# W682A.net
KiCad netlist of a schematic drawn in EAGLE
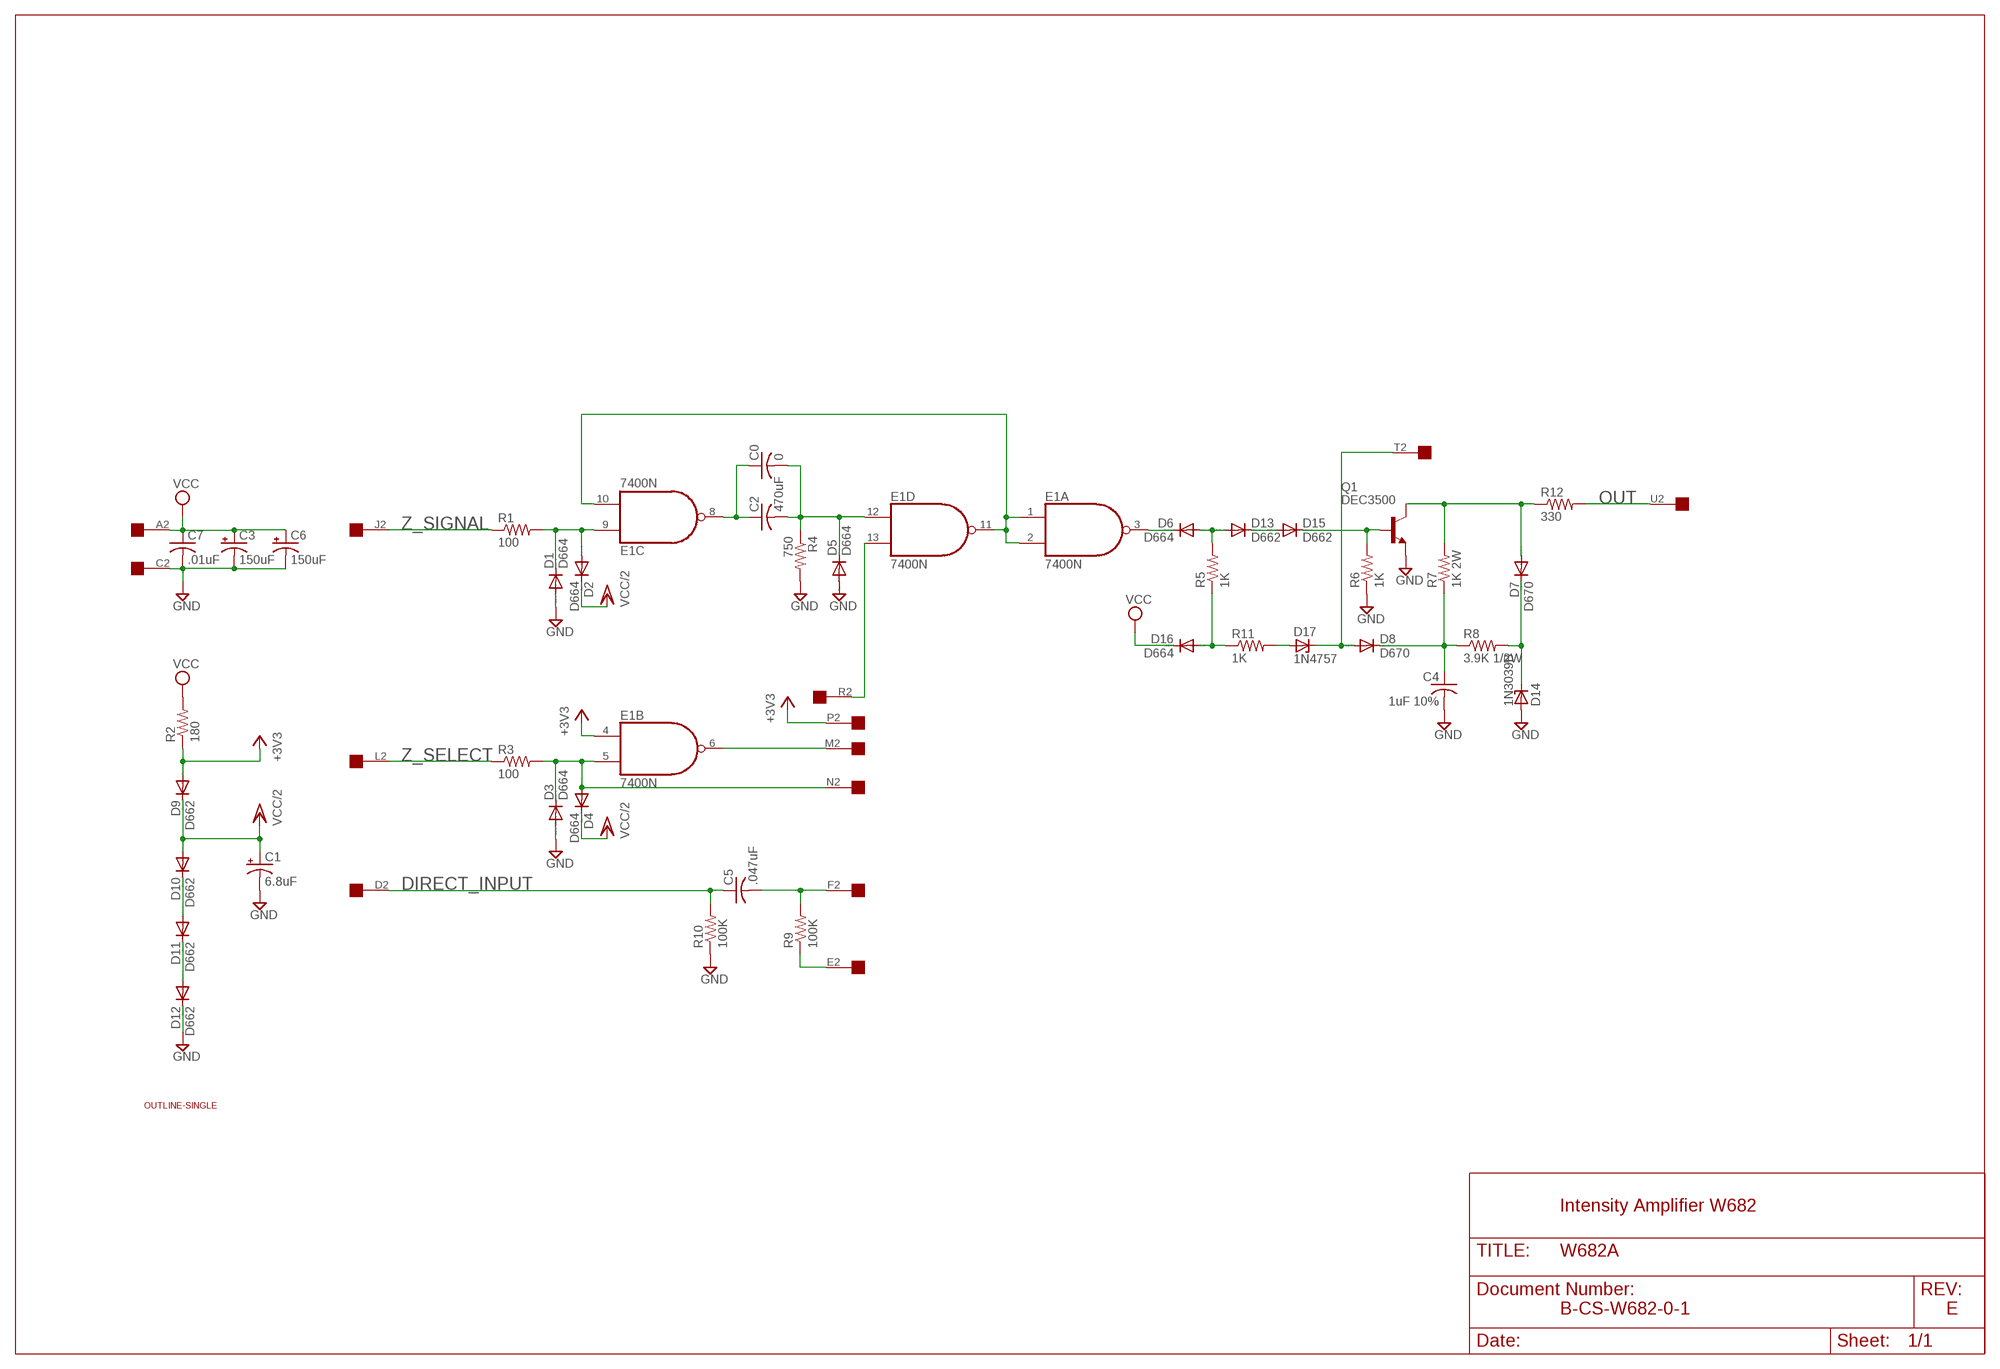
[diagram p0: schematic, sheet 1]

(export (version "E")
  (design (tool "Eeschema 10.0.6"))
  (components
    (comp (ref "C0")
      (value "0")
      (footprint "eagle-import:C050-025X075")
      (libsource (lib "eagle-import") (part "C-US050-025X075"))
    )
    (comp (ref "C1")
      (value "6.8uF")
      (footprint "eagle-import:E12-8")
      (libsource (lib "eagle-import") (part "CPOL-USE20-8AXIAL"))
    )
    (comp (ref "C2")
      (value "470uF")
      (footprint "eagle-import:C050-025X075")
      (libsource (lib "eagle-import") (part "C-US050-025X075"))
    )
    (comp (ref "C3")
      (value "150uF")
      (footprint "eagle-import:E22-9")
      (libsource (lib "eagle-import") (part "CPOL-USE22-9AXIAL"))
    )
    (comp (ref "C4")
      (value "1uF 10%")
      (footprint "eagle-import:C325-137X374")
      (libsource (lib "eagle-import") (part "C-US325-137X374"))
    )
    (comp (ref "C5")
      (value ".047uF")
      (footprint "eagle-import:C275-093X316")
      (libsource (lib "eagle-import") (part "C-US275-093X316"))
    )
    (comp (ref "C6")
      (value "150uF")
      (footprint "eagle-import:E22-9")
      (libsource (lib "eagle-import") (part "CPOL-USE22-9AXIAL"))
    )
    (comp (ref "C7")
      (value ".01uF")
      (footprint "eagle-import:C050-025X075")
      (libsource (lib "eagle-import") (part "C-US050-025X075"))
    )
    (comp (ref "D1")
      (value "D664")
      (footprint "eagle-import:DO35-10")
      (libsource (lib "eagle-import") (part "DIODE-DO35-10"))
    )
    (comp (ref "D2")
      (value "D664")
      (footprint "eagle-import:DO35-10")
      (libsource (lib "eagle-import") (part "DIODE-DO35-10"))
    )
    (comp (ref "D3")
      (value "D664")
      (footprint "eagle-import:DO35-10")
      (libsource (lib "eagle-import") (part "DIODE-DO35-10"))
    )
    (comp (ref "D4")
      (value "D664")
      (footprint "eagle-import:DO35-10")
      (libsource (lib "eagle-import") (part "DIODE-DO35-10"))
    )
    (comp (ref "D5")
      (value "D664")
      (footprint "eagle-import:DO35-10")
      (libsource (lib "eagle-import") (part "DIODE-DO35-10"))
    )
    (comp (ref "D6")
      (value "D664")
      (footprint "eagle-import:DO35-10")
      (libsource (lib "eagle-import") (part "DIODE-DO35-10"))
    )
    (comp (ref "D7")
      (value "D670")
      (footprint "eagle-import:DO41-10")
      (libsource (lib "eagle-import") (part "DIODE-DO41-10"))
    )
    (comp (ref "D8")
      (value "D670")
      (footprint "eagle-import:DO41-10")
      (libsource (lib "eagle-import") (part "DIODE-DO41-10"))
    )
    (comp (ref "D9")
      (value "D662")
      (footprint "eagle-import:DO35-10")
      (libsource (lib "eagle-import") (part "DIODE-DO35-10"))
    )
    (comp (ref "D10")
      (value "D662")
      (footprint "eagle-import:DO35-10")
      (libsource (lib "eagle-import") (part "DIODE-DO35-10"))
    )
    (comp (ref "D11")
      (value "D662")
      (footprint "eagle-import:DO35-10")
      (libsource (lib "eagle-import") (part "DIODE-DO35-10"))
    )
    (comp (ref "D12")
      (value "D662")
      (footprint "eagle-import:DO35-10")
      (libsource (lib "eagle-import") (part "DIODE-DO35-10"))
    )
    (comp (ref "D13")
      (value "D662")
      (footprint "eagle-import:DO35-10")
      (libsource (lib "eagle-import") (part "DIODE-DO35-10"))
    )
    (comp (ref "D14")
      (value "1N3039B")
      (footprint "eagle-import:ZDIO12.5")
      (libsource (lib "eagle-import") (part "ZENER-DIODEZD-12.5"))
    )
    (comp (ref "D15")
      (value "D662")
      (footprint "eagle-import:DO35-10")
      (libsource (lib "eagle-import") (part "DIODE-DO35-10"))
    )
    (comp (ref "D16")
      (value "D664")
      (footprint "eagle-import:DO35-10")
      (libsource (lib "eagle-import") (part "DIODE-DO35-10"))
    )
    (comp (ref "D17")
      (value "1N4757")
      (footprint "eagle-import:ZDIO12.5")
      (libsource (lib "eagle-import") (part "ZENER-DIODEZD-12.5"))
    )
    (comp (ref "E1")
      (value "7400N")
      (footprint "eagle-import:DIL14")
      (libsource (lib "eagle-import") (part "7400N"))
    )
    (comp (ref "Q1")
      (value "DEC3500")
      (footprint "eagle-import:TO39")
      (libsource (lib "eagle-import") (part "-NPN-TO39-EBC2N2102"))
    )
    (comp (ref "R1")
      (value "100")
      (footprint "eagle-import:0207_10")
      (libsource (lib "eagle-import") (part "R-US_0207/10"))
    )
    (comp (ref "R2")
      (value "180")
      (footprint "eagle-import:0207_10")
      (libsource (lib "eagle-import") (part "R-US_0207/10"))
    )
    (comp (ref "R3")
      (value "100")
      (footprint "eagle-import:0207_10")
      (libsource (lib "eagle-import") (part "R-US_0207/10"))
    )
    (comp (ref "R4")
      (value "750")
      (footprint "eagle-import:0207_10")
      (libsource (lib "eagle-import") (part "R-US_0207/10"))
    )
    (comp (ref "R5")
      (value "1K")
      (footprint "eagle-import:0207_10")
      (libsource (lib "eagle-import") (part "R-US_0207/10"))
    )
    (comp (ref "R6")
      (value "1K")
      (footprint "eagle-import:0207_10")
      (libsource (lib "eagle-import") (part "R-US_0207/10"))
    )
    (comp (ref "R7")
      (value "1K 2W")
      (footprint "eagle-import:0818_25")
      (libsource (lib "eagle-import") (part "R-US_0818/25"))
    )
    (comp (ref "R8")
      (value "3.9K 1/2W")
      (footprint "eagle-import:0411_15")
      (libsource (lib "eagle-import") (part "R-US_0411/15"))
    )
    (comp (ref "R9")
      (value "100K")
      (footprint "eagle-import:0207_10")
      (libsource (lib "eagle-import") (part "R-US_0207/10"))
    )
    (comp (ref "R10")
      (value "100K")
      (footprint "eagle-import:0207_10")
      (libsource (lib "eagle-import") (part "R-US_0207/10"))
    )
    (comp (ref "R11")
      (value "1K")
      (footprint "eagle-import:0207_10")
      (libsource (lib "eagle-import") (part "R-US_0207/10"))
    )
    (comp (ref "R12")
      (value "330")
      (footprint "eagle-import:0207_10")
      (libsource (lib "eagle-import") (part "R-US_0207/10"))
    )
    (comp (ref "U$1")
      (value "OUTLINE-SINGLE")
      (footprint "eagle-import:SINGLE")
      (libsource (lib "eagle-import") (part "OUTLINE-SINGLE"))
    )
    (comp (ref "U$2")
      (value "EDGE-1")
      (footprint "eagle-import:EDGE-CON1")
      (libsource (lib "eagle-import") (part "EDGE-1"))
    )
  )
  (nets
    (net (code "1") (name "+3V3") (class "Default")
      (node (ref "D9") (pin "A") (pinfunction "A_A") (pintype "passive"))
      (node (ref "E1") (pin "4") (pinfunction "I0_4") (pintype "input"))
      (node (ref "R2") (pin "1") (pinfunction "1_1") (pintype "passive"))
      (node (ref "U$2") (pin "P2") (pinfunction "1_P2") (pintype "bidirectional"))
    )
    (net (code "2") (name "/DIRECT_INPUT") (class "Default")
      (node (ref "C5") (pin "1") (pinfunction "1_1") (pintype "passive"))
      (node (ref "R10") (pin "2") (pinfunction "2_2") (pintype "passive"))
      (node (ref "U$2") (pin "D2") (pinfunction "1_D2") (pintype "bidirectional"))
    )
    (net (code "3") (name "/OUT") (class "Default")
      (node (ref "R12") (pin "2") (pinfunction "2_2") (pintype "passive"))
      (node (ref "U$2") (pin "U2") (pinfunction "1_U2") (pintype "bidirectional"))
    )
    (net (code "4") (name "/Z_SELECT") (class "Default")
      (node (ref "R3") (pin "1") (pinfunction "1_1") (pintype "passive"))
      (node (ref "U$2") (pin "L2") (pinfunction "1_L2") (pintype "bidirectional"))
    )
    (net (code "5") (name "/Z_SIGNAL") (class "Default")
      (node (ref "R1") (pin "1") (pinfunction "1_1") (pintype "passive"))
      (node (ref "U$2") (pin "J2") (pinfunction "1_J2") (pintype "bidirectional"))
    )
    (net (code "6") (name "GND") (class "Default")
      (node (ref "C1") (pin "-") (pinfunction "-_-") (pintype "passive"))
      (node (ref "C3") (pin "-") (pinfunction "-_-") (pintype "passive"))
      (node (ref "C4") (pin "2") (pinfunction "2_2") (pintype "passive"))
      (node (ref "C6") (pin "-") (pinfunction "-_-") (pintype "passive"))
      (node (ref "C7") (pin "2") (pinfunction "2_2") (pintype "passive"))
      (node (ref "D1") (pin "A") (pinfunction "A_A") (pintype "passive"))
      (node (ref "D12") (pin "C") (pinfunction "C_C") (pintype "passive"))
      (node (ref "D14") (pin "A") (pinfunction "A_A") (pintype "passive"))
      (node (ref "D3") (pin "A") (pinfunction "A_A") (pintype "passive"))
      (node (ref "D5") (pin "A") (pinfunction "A_A") (pintype "passive"))
      (node (ref "Q1") (pin "1") (pinfunction "E_1") (pintype "passive"))
      (node (ref "R10") (pin "1") (pinfunction "1_1") (pintype "passive"))
      (node (ref "R4") (pin "2") (pinfunction "2_2") (pintype "passive"))
      (node (ref "R6") (pin "1") (pinfunction "1_1") (pintype "passive"))
      (node (ref "U$2") (pin "C2") (pinfunction "1_C2") (pintype "bidirectional"))
    )
    (net (code "7") (name "Net-(C4-Pad1)") (class "Default")
      (node (ref "C4") (pin "1") (pinfunction "1_1") (pintype "passive"))
      (node (ref "D8") (pin "C") (pinfunction "C_C") (pintype "passive"))
      (node (ref "R7") (pin "1") (pinfunction "1_1") (pintype "passive"))
      (node (ref "R8") (pin "1") (pinfunction "1_1") (pintype "passive"))
    )
    (net (code "8") (name "Net-(D10-PadC)") (class "Default")
      (node (ref "D10") (pin "C") (pinfunction "C_C") (pintype "passive"))
      (node (ref "D11") (pin "A") (pinfunction "A_A") (pintype "passive"))
    )
    (net (code "9") (name "Net-(D11-PadC)") (class "Default")
      (node (ref "D11") (pin "C") (pinfunction "C_C") (pintype "passive"))
      (node (ref "D12") (pin "A") (pinfunction "A_A") (pintype "passive"))
    )
    (net (code "10") (name "Net-(D13-PadA)") (class "Default")
      (node (ref "D13") (pin "A") (pinfunction "A_A") (pintype "passive"))
      (node (ref "D6") (pin "A") (pinfunction "A_A") (pintype "passive"))
      (node (ref "R5") (pin "2") (pinfunction "2_2") (pintype "passive"))
    )
    (net (code "11") (name "Net-(D13-PadC)") (class "Default")
      (node (ref "D13") (pin "C") (pinfunction "C_C") (pintype "passive"))
      (node (ref "D15") (pin "A") (pinfunction "A_A") (pintype "passive"))
    )
    (net (code "12") (name "Net-(D14-PadC)") (class "Default")
      (node (ref "D14") (pin "C") (pinfunction "C_C") (pintype "passive"))
      (node (ref "D7") (pin "C") (pinfunction "C_C") (pintype "passive"))
      (node (ref "R8") (pin "2") (pinfunction "2_2") (pintype "passive"))
    )
    (net (code "13") (name "Net-(D16-PadA)") (class "Default")
      (node (ref "D16") (pin "A") (pinfunction "A_A") (pintype "passive"))
      (node (ref "R11") (pin "1") (pinfunction "1_1") (pintype "passive"))
      (node (ref "R5") (pin "1") (pinfunction "1_1") (pintype "passive"))
    )
    (net (code "14") (name "Net-(D17-PadA)") (class "Default")
      (node (ref "D17") (pin "A") (pinfunction "A_A") (pintype "passive"))
      (node (ref "R11") (pin "2") (pinfunction "2_2") (pintype "passive"))
    )
    (net (code "15") (name "Net-(E1A-I0)") (class "Default")
      (node (ref "E1") (pin "1") (pinfunction "I0_1") (pintype "input"))
      (node (ref "E1") (pin "10") (pinfunction "I1_10") (pintype "input"))
      (node (ref "E1") (pin "11") (pinfunction "O_11") (pintype "output"))
      (node (ref "E1") (pin "2") (pinfunction "I1_2") (pintype "input"))
    )
    (net (code "16") (name "Net-(E1A-O)") (class "Default")
      (node (ref "D6") (pin "C") (pinfunction "C_C") (pintype "passive"))
      (node (ref "E1") (pin "3") (pinfunction "O_3") (pintype "output"))
    )
    (net (code "17") (name "Net-(E1B-I1)") (class "Default")
      (node (ref "D3") (pin "C") (pinfunction "C_C") (pintype "passive"))
      (node (ref "D4") (pin "A") (pinfunction "A_A") (pintype "passive"))
      (node (ref "E1") (pin "5") (pinfunction "I1_5") (pintype "input"))
      (node (ref "R3") (pin "2") (pinfunction "2_2") (pintype "passive"))
      (node (ref "U$2") (pin "N2") (pinfunction "1_N2") (pintype "bidirectional"))
    )
    (net (code "18") (name "Net-(E1B-O)") (class "Default")
      (node (ref "E1") (pin "6") (pinfunction "O_6") (pintype "output"))
      (node (ref "U$2") (pin "M2") (pinfunction "1_M2") (pintype "bidirectional"))
    )
    (net (code "19") (name "Net-(E1C-I0)") (class "Default")
      (node (ref "D1") (pin "C") (pinfunction "C_C") (pintype "passive"))
      (node (ref "D2") (pin "A") (pinfunction "A_A") (pintype "passive"))
      (node (ref "E1") (pin "9") (pinfunction "I0_9") (pintype "input"))
      (node (ref "R1") (pin "2") (pinfunction "2_2") (pintype "passive"))
    )
    (net (code "20") (name "Net-(E1C-O)") (class "Default")
      (node (ref "C0") (pin "1") (pinfunction "1_1") (pintype "passive"))
      (node (ref "C2") (pin "1") (pinfunction "1_1") (pintype "passive"))
      (node (ref "E1") (pin "8") (pinfunction "O_8") (pintype "output"))
    )
    (net (code "21") (name "Net-(E1D-I0)") (class "Default")
      (node (ref "C0") (pin "2") (pinfunction "2_2") (pintype "passive"))
      (node (ref "C2") (pin "2") (pinfunction "2_2") (pintype "passive"))
      (node (ref "D5") (pin "C") (pinfunction "C_C") (pintype "passive"))
      (node (ref "E1") (pin "12") (pinfunction "I0_12") (pintype "input"))
      (node (ref "R4") (pin "1") (pinfunction "1_1") (pintype "passive"))
    )
    (net (code "22") (name "Net-(E1D-I1)") (class "Default")
      (node (ref "E1") (pin "13") (pinfunction "I1_13") (pintype "input"))
      (node (ref "U$2") (pin "R2") (pinfunction "1_R2") (pintype "bidirectional"))
    )
    (net (code "23") (name "Net-(Q1-B)") (class "Default")
      (node (ref "D15") (pin "C") (pinfunction "C_C") (pintype "passive"))
      (node (ref "Q1") (pin "2") (pinfunction "B_2") (pintype "passive"))
      (node (ref "R6") (pin "2") (pinfunction "2_2") (pintype "passive"))
    )
    (net (code "24") (name "Net-(Q1-C)") (class "Default")
      (node (ref "D7") (pin "A") (pinfunction "A_A") (pintype "passive"))
      (node (ref "Q1") (pin "3") (pinfunction "C_3") (pintype "passive"))
      (node (ref "R12") (pin "1") (pinfunction "1_1") (pintype "passive"))
      (node (ref "R7") (pin "2") (pinfunction "2_2") (pintype "passive"))
    )
    (net (code "25") (name "Net-(U$2E-1)") (class "Default")
      (node (ref "R9") (pin "1") (pinfunction "1_1") (pintype "passive"))
      (node (ref "U$2") (pin "E2") (pinfunction "1_E2") (pintype "bidirectional"))
    )
    (net (code "26") (name "Net-(U$2F-1)") (class "Default")
      (node (ref "C5") (pin "2") (pinfunction "2_2") (pintype "passive"))
      (node (ref "R9") (pin "2") (pinfunction "2_2") (pintype "passive"))
      (node (ref "U$2") (pin "F2") (pinfunction "1_F2") (pintype "bidirectional"))
    )
    (net (code "27") (name "Net-(U$2P-1)") (class "Default")
      (node (ref "D17") (pin "C") (pinfunction "C_C") (pintype "passive"))
      (node (ref "D8") (pin "A") (pinfunction "A_A") (pintype "passive"))
      (node (ref "U$2") (pin "T2") (pinfunction "1_T2") (pintype "bidirectional"))
    )
    (net (code "28") (name "VCC") (class "Default")
      (node (ref "C3") (pin "+") (pinfunction "+_+") (pintype "passive"))
      (node (ref "C6") (pin "+") (pinfunction "+_+") (pintype "passive"))
      (node (ref "C7") (pin "1") (pinfunction "1_1") (pintype "passive"))
      (node (ref "D16") (pin "C") (pinfunction "C_C") (pintype "passive"))
      (node (ref "R2") (pin "2") (pinfunction "2_2") (pintype "passive"))
      (node (ref "U$2") (pin "A2") (pinfunction "1_A2") (pintype "bidirectional"))
    )
    (net (code "29") (name "VCC{slash}2") (class "Default")
      (node (ref "C1") (pin "+") (pinfunction "+_+") (pintype "passive"))
      (node (ref "D10") (pin "A") (pinfunction "A_A") (pintype "passive"))
      (node (ref "D2") (pin "C") (pinfunction "C_C") (pintype "passive"))
      (node (ref "D4") (pin "C") (pinfunction "C_C") (pintype "passive"))
      (node (ref "D9") (pin "C") (pinfunction "C_C") (pintype "passive"))
    )
  )
)
